# eFuse_Slave_Supply.net
KiCad netlist of a schematic drawn in Altium Designer
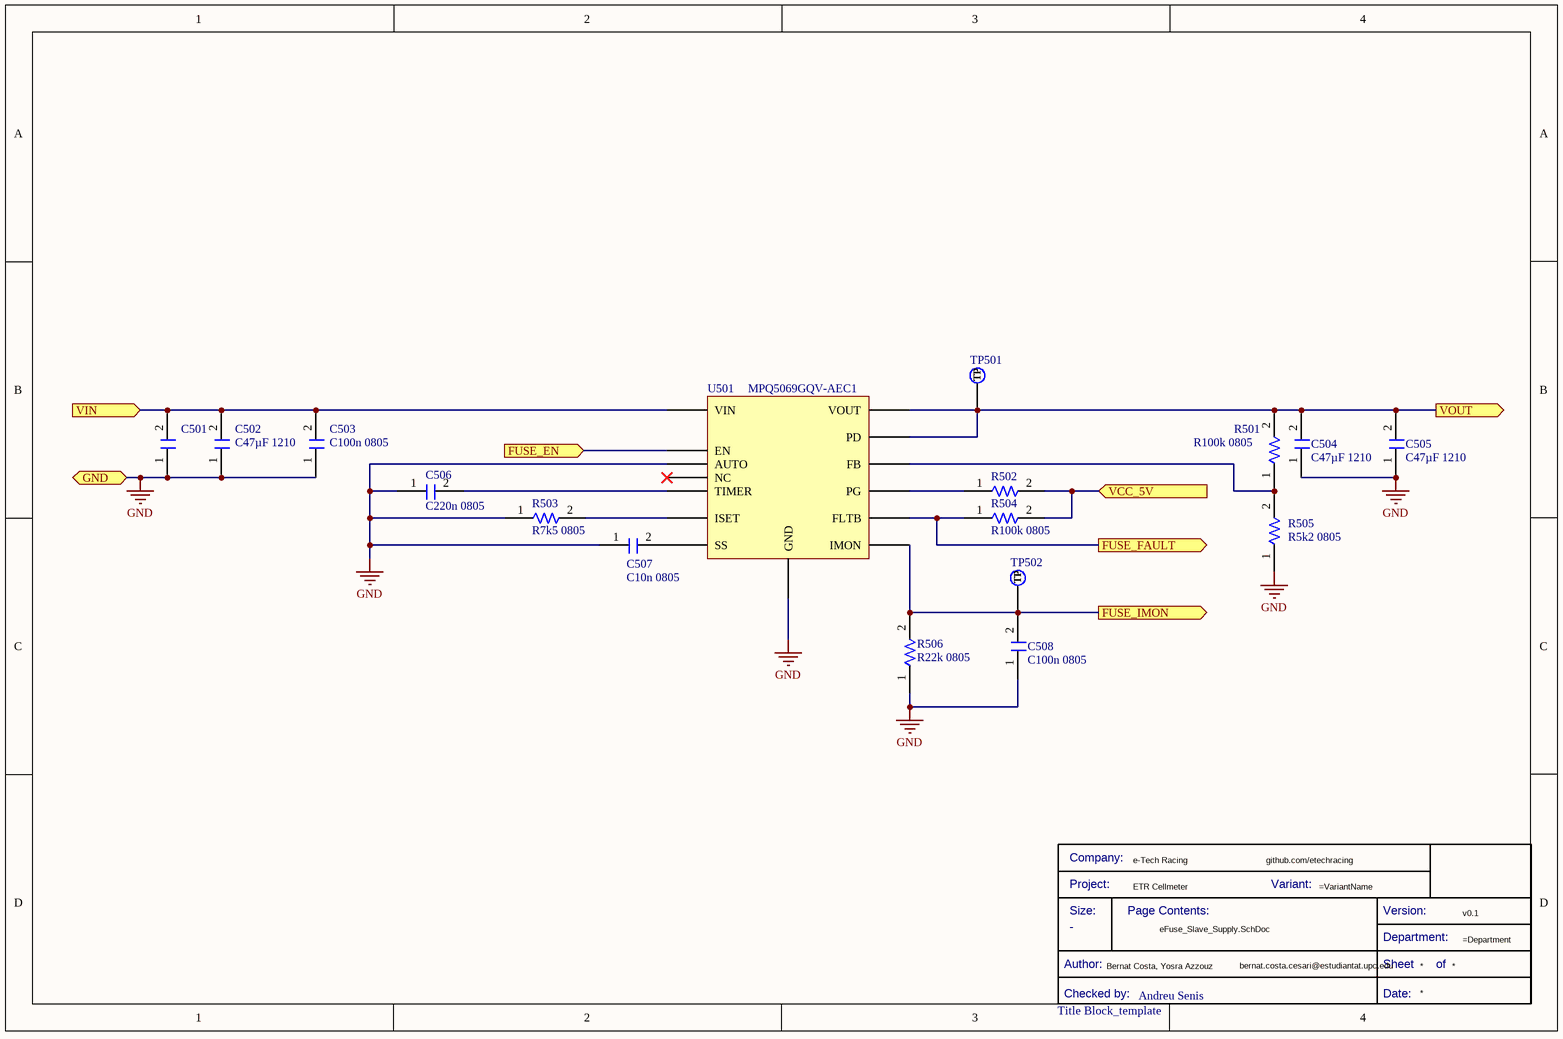
[diagram p0: eFuse_Slave_Supply.SchDoc]

(export (version "E")
  (design (tool "Eeschema 10.0.6"))
  (components
    (comp (ref "C501")
      (value "C47µF-10V-1210")
      (footprint "FP-GRM32E-0_3-0_2-IPC_C")
      (libsource (lib "EMEA- E-Tech Racing- I'Escola d'Enginyeria de Barcelona Est") (part "C100p-50V-0805FNPC-C0G/NP0"))
    )
    (comp (ref "C502")
      (value "C47µF 1210")
      (footprint "FP-GRM32E-0_3-0_2-IPC_C")
      (libsource (lib "EMEA- E-Tech Racing- I'Escola d'Enginyeria de Barcelona Est") (part "C100p-50V-0805FNPC-C0G/NP0"))
    )
    (comp (ref "C503")
      (value "C100n 0805")
      (footprint "C0805FNPC-R")
      (description "Cap, 0.1ΜF, 50V, 10%, X7R, 0805")
      (fields (field (name "TOLERANCE") "10%") (field (name ".CREATOR") "DR"))
      (libsource (lib "EMEA- E-Tech Racing- I'Escola d'Enginyeria de Barcelona Est") (part "C100p-50V-0805FNPC-C0G/NP0"))
    )
    (comp (ref "C504")
      (value "C47µF 1210")
      (footprint "FP-GRM32E-0_3-0_2-IPC_C")
      (libsource (lib "EMEA- E-Tech Racing- I'Escola d'Enginyeria de Barcelona Est") (part "C100p-50V-0805FNPC-C0G/NP0"))
    )
    (comp (ref "C505")
      (value "C47µF 1210")
      (footprint "FP-GRM32E-0_3-0_2-IPC_C")
      (libsource (lib "EMEA- E-Tech Racing- I'Escola d'Enginyeria de Barcelona Est") (part "C100p-50V-0805FNPC-C0G/NP0"))
    )
    (comp (ref "C506")
      (value "C220n 0805")
      (footprint "C0805FNPC-W")
      (description "Cap Ceramic 0.22uF 50V X5R 10% Pad SMD 0805 85C Low ESR Automotive T/R")
      (fields
        (field (name "TOLERANCE") "10%")
        (field (name "MANUFACTURER") "Taiyo Yuden")
        (field (name ".CREATOR") "DR")
      )
      (libsource (lib "EMEA- E-Tech Racing- I'Escola d'Enginyeria de Barcelona Est") (part "C100p-50V-0805FNPC-C0G/NP0"))
    )
    (comp (ref "C507")
      (value "C10n 0805")
      (footprint "C0805FNPC-R")
      (description "Cap, 0.01ΜF, 50V, 10%, X7R, 0805")
      (fields (field (name "TOLERANCE") "10%") (field (name ".CREATOR") "DR"))
      (libsource (lib "EMEA- E-Tech Racing- I'Escola d'Enginyeria de Barcelona Est") (part "C100p-50V-0805FNPC-C0G/NP0"))
    )
    (comp (ref "C508")
      (value "C100n 0805")
      (footprint "C0805FNPC-R")
      (description "Cap, 0.1ΜF, 50V, 10%, X7R, 0805")
      (fields (field (name "TOLERANCE") "10%") (field (name ".CREATOR") "DR"))
      (libsource (lib "EMEA- E-Tech Racing- I'Escola d'Enginyeria de Barcelona Est") (part "C100p-50V-0805FNPC-C0G/NP0"))
    )
    (comp (ref "R501")
      (value "R100k 0805")
      (footprint "RESC2013X70X40NL20T20")
      (fields (field (name "POWER") "125mW") (field (name "TOLERANCE") "5%"))
      (libsource (lib "EMEA- E-Tech Racing- I'Escola d'Enginyeria de Barcelona Est") (part "R9.09K-1206FTK"))
    )
    (comp (ref "R502")
      (value "R100k 0805")
      (footprint "RESC2013X70X40NL20T20")
      (fields (field (name "POWER") "125mW") (field (name "TOLERANCE") "5%"))
      (libsource (lib "EMEA- E-Tech Racing- I'Escola d'Enginyeria de Barcelona Est") (part "R9.09K-1206FTK"))
    )
    (comp (ref "R503")
      (value "R7k5 0805")
      (footprint "RESC2013X50X30ML20T20")
      (fields (field (name "POWER") "125mW") (field (name "TOLERANCE") "1%"))
      (libsource (lib "EMEA- E-Tech Racing- I'Escola d'Enginyeria de Barcelona Est") (part "R9.09K-1206FTK"))
    )
    (comp (ref "R504")
      (value "R100k 0805")
      (footprint "RESC2013X70X40NL20T20")
      (fields (field (name "POWER") "125mW") (field (name "TOLERANCE") "5%"))
      (libsource (lib "EMEA- E-Tech Racing- I'Escola d'Enginyeria de Barcelona Est") (part "R9.09K-1206FTK"))
    )
    (comp (ref "R505")
      (value "R5k2 0805")
      (footprint "RESC2013X70X40NL20T20")
      (fields (field (name "POWER") "125mW") (field (name "TOLERANCE") "5%"))
      (libsource (lib "EMEA- E-Tech Racing- I'Escola d'Enginyeria de Barcelona Est") (part "R9.09K-1206FTK"))
    )
    (comp (ref "R506")
      (value "R22k 0805")
      (footprint "RESC2013X70X40NL20T20")
      (fields (field (name "POWER") "125mW") (field (name "TOLERANCE") "5%"))
      (libsource (lib "EMEA- E-Tech Racing- I'Escola d'Enginyeria de Barcelona Est") (part "R9.09K-1206FTK"))
    )
    (comp (ref "TP501")
      (value "TestPoint")
      (footprint "TestPoint")
      (description "Test Point 1x1 mm")
      (fields (field (name ".SCHCHECK") "GP") (field (name ".CREATOR") "GP") (field (name ".PCBCHECK") "GP"))
      (libsource (lib "EMEA- E-Tech Racing- I'Escola d'Enginyeria de Barcelona Est") (part "TestPoint"))
    )
    (comp (ref "TP502")
      (value "TestPoint")
      (footprint "TestPoint")
      (description "Test Point 1x1 mm")
      (fields (field (name ".SCHCHECK") "GP") (field (name ".CREATOR") "GP") (field (name ".PCBCHECK") "GP"))
      (libsource (lib "EMEA- E-Tech Racing- I'Escola d'Enginyeria de Barcelona Est") (part "TestPoint"))
    )
    (comp (ref "U501")
      (value "MPQ5069GQV-AEC1")
      (footprint "QFN127P600-8N")
      (description "7mΩ Protection Switch with Current Monitor for Automotive Battery Systems AEC-Q100 Qualified")
      (libsource (lib "EMEA- E-Tech Racing- I'Escola d'Enginyeria de Barcelona Est") (part "MPQ5069GQV-AEC1"))
    )
  )
  (nets
    (net (code "1") (name "/FUSE_EN") (class "Default")
      (node (ref "U501") (pin "2") (pinfunction "EN_2") (pintype "passive"))
    )
    (net (code "2") (name "/FUSE_FAULT") (class "Default")
      (node (ref "R504") (pin "1") (pinfunction "1_1") (pintype "passive"))
      (node (ref "U501") (pin "10") (pinfunction "FLTB_10") (pintype "passive"))
    )
    (net (code "3") (name "/FUSE_IMON") (class "Default")
      (node (ref "C508") (pin "2") (pinfunction "2_2") (pintype "passive"))
      (node (ref "R506") (pin "2") (pinfunction "2_2") (pintype "passive"))
      (node (ref "TP502") (pin "1") (pinfunction "TP_1") (pintype "passive"))
      (node (ref "U501") (pin "9") (pinfunction "IMON_9") (pintype "passive"))
    )
    (net (code "4") (name "/VCC_5V") (class "Default")
      (node (ref "R502") (pin "2") (pinfunction "2_2") (pintype "passive"))
      (node (ref "R504") (pin "2") (pinfunction "2_2") (pintype "passive"))
    )
    (net (code "5") (name "/VIN") (class "Default")
      (node (ref "C501") (pin "2") (pinfunction "2_2") (pintype "passive"))
      (node (ref "C502") (pin "2") (pinfunction "2_2") (pintype "passive"))
      (node (ref "C503") (pin "2") (pinfunction "2_2") (pintype "passive"))
      (node (ref "U501") (pin "1") (pinfunction "VIN_1") (pintype "passive"))
    )
    (net (code "6") (name "/VOUT") (class "Default")
      (node (ref "C504") (pin "2") (pinfunction "2_2") (pintype "passive"))
      (node (ref "C505") (pin "2") (pinfunction "2_2") (pintype "passive"))
      (node (ref "R501") (pin "2") (pinfunction "2_2") (pintype "passive"))
      (node (ref "TP501") (pin "1") (pinfunction "TP_1") (pintype "passive"))
      (node (ref "U501") (pin "13") (pinfunction "PD_13") (pintype "passive"))
      (node (ref "U501") (pin "14") (pinfunction "VOUT_14") (pintype "passive"))
    )
    (net (code "7") (name "GND") (class "Default")
      (node (ref "C501") (pin "1") (pinfunction "1_1") (pintype "passive"))
      (node (ref "C502") (pin "1") (pinfunction "1_1") (pintype "passive"))
      (node (ref "C503") (pin "1") (pinfunction "1_1") (pintype "passive"))
      (node (ref "C504") (pin "1") (pinfunction "1_1") (pintype "passive"))
      (node (ref "C505") (pin "1") (pinfunction "1_1") (pintype "passive"))
      (node (ref "C506") (pin "1") (pinfunction "1_1") (pintype "passive"))
      (node (ref "C507") (pin "1") (pinfunction "1_1") (pintype "passive"))
      (node (ref "C508") (pin "1") (pinfunction "1_1") (pintype "passive"))
      (node (ref "R503") (pin "1") (pinfunction "1_1") (pintype "passive"))
      (node (ref "R505") (pin "1") (pinfunction "1_1") (pintype "passive"))
      (node (ref "R506") (pin "1") (pinfunction "1_1") (pintype "passive"))
      (node (ref "U501") (pin "3") (pinfunction "AUTO_3") (pintype "passive"))
      (node (ref "U501") (pin "8") (pinfunction "GND_8") (pintype "passive"))
    )
    (net (code "8") (name "Net-(U501-FB)") (class "Default")
      (node (ref "R501") (pin "1") (pinfunction "1_1") (pintype "passive"))
      (node (ref "R505") (pin "2") (pinfunction "2_2") (pintype "passive"))
      (node (ref "U501") (pin "12") (pinfunction "FB_12") (pintype "passive"))
    )
    (net (code "9") (name "Net-(U501-ISET)") (class "Default")
      (node (ref "R503") (pin "2") (pinfunction "2_2") (pintype "passive"))
      (node (ref "U501") (pin "6") (pinfunction "ISET_6") (pintype "passive"))
    )
    (net (code "10") (name "Net-(U501-PG)") (class "Default")
      (node (ref "R502") (pin "1") (pinfunction "1_1") (pintype "passive"))
      (node (ref "U501") (pin "11") (pinfunction "PG_11") (pintype "passive"))
    )
    (net (code "11") (name "Net-(U501-SS)") (class "Default")
      (node (ref "C507") (pin "2") (pinfunction "2_2") (pintype "passive"))
      (node (ref "U501") (pin "7") (pinfunction "SS_7") (pintype "passive"))
    )
    (net (code "12") (name "Net-(U501-TIMER)") (class "Default")
      (node (ref "C506") (pin "2") (pinfunction "2_2") (pintype "passive"))
      (node (ref "U501") (pin "5") (pinfunction "TIMER_5") (pintype "passive"))
    )
    (net (code "13") (name "unconnected-(U501-NC-Pad4)") (class "Default")
      (node (ref "U501") (pin "4") (pinfunction "NC_4") (pintype "passive+no_connect"))
    )
  )
)
